# Tempy.net
KiCad netlist of a schematic drawn in EAGLE
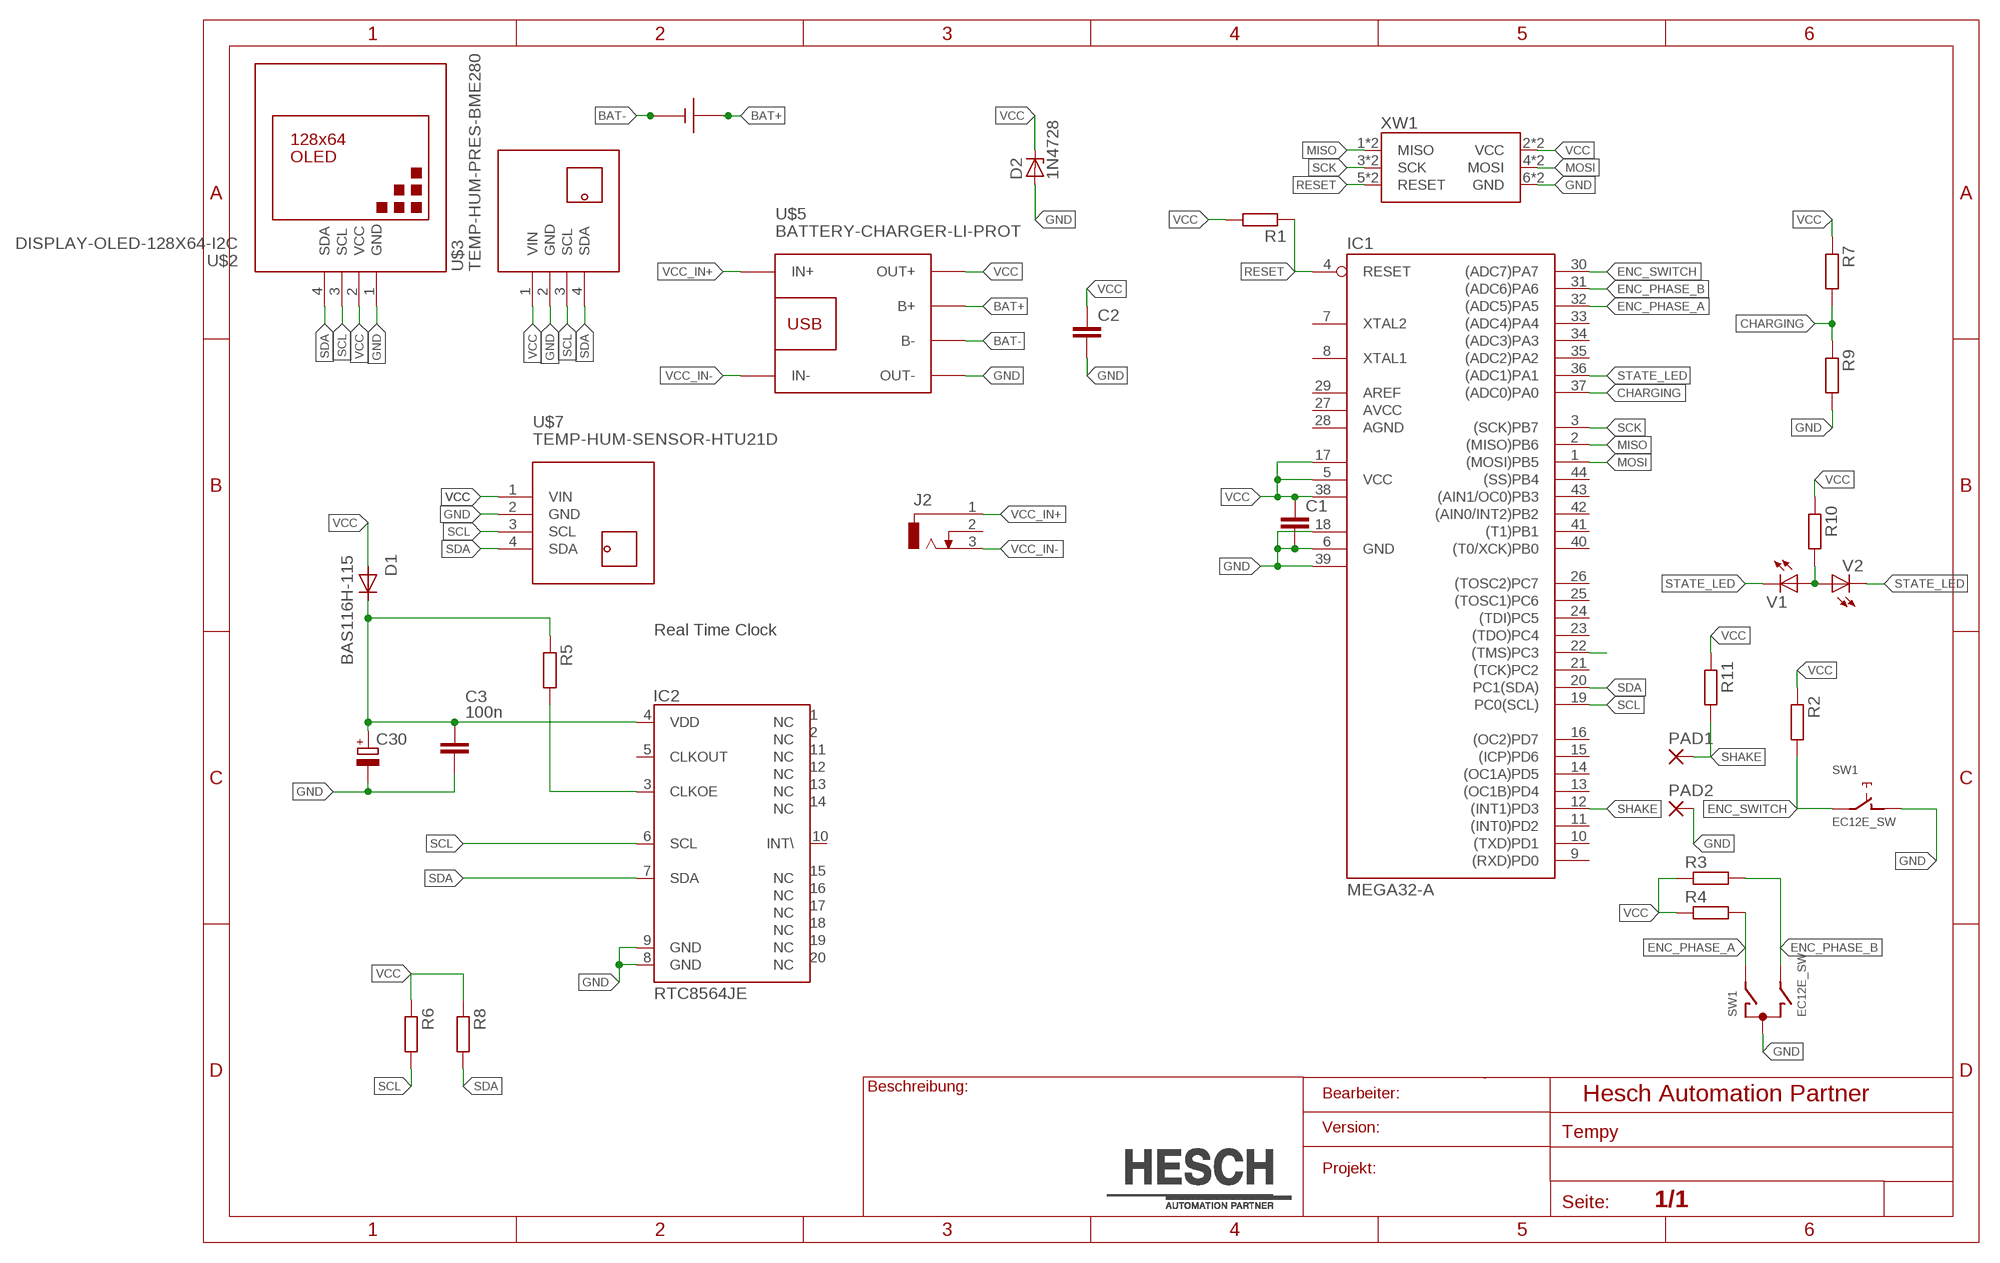
[diagram p0: schematic, sheet 1]

(export (version "E")
  (design (tool "Eeschema 10.0.6"))
  (components
    (comp (ref "C1")
      (value "C-EUC0805K")
      (footprint "eagle-import:C0805K")
      (libsource (lib "eagle-import") (part "C-EUC0805K"))
    )
    (comp (ref "C2")
      (value "C-EUC0805K")
      (footprint "eagle-import:C0805K")
      (libsource (lib "eagle-import") (part "C-EUC0805K"))
    )
    (comp (ref "C3")
      (value "100n")
      (footprint "eagle-import:C0805")
      (libsource (lib "eagle-import") (part "C-EUC0805"))
    )
    (comp (ref "C30")
      (value "PANASONIC-EN&SD-SERIESTHT_1")
      (footprint "eagle-import:PANASONIC_SD_SERIES_STEHEND")
      (libsource (lib "eagle-import") (part "PANASONIC-EN&SD-SERIESTHT_1"))
    )
    (comp (ref "D1")
      (value "BAS116H-115")
      (footprint "eagle-import:SOD123")
      (libsource (lib "eagle-import") (part "BAS116H-115"))
    )
    (comp (ref "D2")
      (value "1N4728")
      (footprint "eagle-import:DO41Z10")
      (libsource (lib "eagle-import") (part "1N4728"))
    )
    (comp (ref "IC1")
      (value "MEGA32-A")
      (footprint "eagle-import:TQFP44")
      (libsource (lib "eagle-import") (part "MEGA32-A"))
    )
    (comp (ref "IC2")
      (value "RTC8564JESMD")
      (footprint "eagle-import:VSOJ20")
      (libsource (lib "eagle-import") (part "RTC8564JESMD"))
    )
    (comp (ref "J2")
      (value "DCJ0303")
      (footprint "eagle-import:DCJ0303")
      (libsource (lib "eagle-import") (part "DCJ0303"))
    )
    (comp (ref "PAD1")
      (value "2,15/1,0")
      (footprint "eagle-import:2,15_1,0")
      (libsource (lib "eagle-import") (part "2,15/1,0"))
    )
    (comp (ref "PAD2")
      (value "2,15/1,0")
      (footprint "eagle-import:2,15_1,0")
      (libsource (lib "eagle-import") (part "2,15/1,0"))
    )
    (comp (ref "R1")
      (value "R-EU_R1206")
      (footprint "eagle-import:R1206")
      (libsource (lib "eagle-import") (part "R-EU_R1206"))
    )
    (comp (ref "R2")
      (value "R-EU_R1206")
      (footprint "eagle-import:R1206")
      (libsource (lib "eagle-import") (part "R-EU_R1206"))
    )
    (comp (ref "R3")
      (value "R-EU_R1206")
      (footprint "eagle-import:R1206")
      (libsource (lib "eagle-import") (part "R-EU_R1206"))
    )
    (comp (ref "R4")
      (value "R-EU_R1206")
      (footprint "eagle-import:R1206")
      (libsource (lib "eagle-import") (part "R-EU_R1206"))
    )
    (comp (ref "R5")
      (value "R-EU_R1206")
      (footprint "eagle-import:R1206")
      (libsource (lib "eagle-import") (part "R-EU_R1206"))
    )
    (comp (ref "R6")
      (value "R-EU_R1206")
      (footprint "eagle-import:R1206")
      (libsource (lib "eagle-import") (part "R-EU_R1206"))
    )
    (comp (ref "R7")
      (value "R-EU_R1206")
      (footprint "eagle-import:R1206")
      (libsource (lib "eagle-import") (part "R-EU_R1206"))
    )
    (comp (ref "R8")
      (value "R-EU_R1206")
      (footprint "eagle-import:R1206")
      (libsource (lib "eagle-import") (part "R-EU_R1206"))
    )
    (comp (ref "R9")
      (value "R-EU_R1206")
      (footprint "eagle-import:R1206")
      (libsource (lib "eagle-import") (part "R-EU_R1206"))
    )
    (comp (ref "R10")
      (value "R-EU_R1206")
      (footprint "eagle-import:R1206")
      (libsource (lib "eagle-import") (part "R-EU_R1206"))
    )
    (comp (ref "R11")
      (value "R-EU_R1206")
      (footprint "eagle-import:R1206")
      (libsource (lib "eagle-import") (part "R-EU_R1206"))
    )
    (comp (ref "SW1")
      (value "EC12E_SW")
      (footprint "eagle-import:ALPS_EC12E_SW")
      (fields (field (name "MPN") "EC12E2424407"))
      (libsource (lib "eagle-import") (part "EC12E_SW"))
    )
    (comp (ref "U$2")
      (value "DISPLAY-OLED-128X64-I2C")
      (footprint "eagle-import:DISPLAY-OLED-128X64-I2C")
      (libsource (lib "eagle-import") (part "DISPLAY-OLED-128X64-I2C"))
    )
    (comp (ref "U$3")
      (value "TEMP-HUM-PRES-BME280")
      (footprint "eagle-import:TEMP-HUM-PRES-BME280")
      (libsource (lib "eagle-import") (part "TEMP-HUM-PRES-BME280"))
    )
    (comp (ref "U$5")
      (value "BATTERY-CHARGER-LI-PROT")
      (footprint "eagle-import:BATTERY-CHARGER-LI-PROT")
      (libsource (lib "eagle-import") (part "BATTERY-CHARGER-LI-PROT"))
    )
    (comp (ref "U$7")
      (value "TEMP-HUM-SENSOR-HTU21D")
      (footprint "eagle-import:TEMP-HUM-SENSOR-HTU21D")
      (libsource (lib "eagle-import") (part "TEMP-HUM-SENSOR-HTU21D"))
    )
    (comp (ref "U$8")
      (value "18650PTH")
      (footprint "eagle-import:18650-CASE-PTH")
      (libsource (lib "eagle-import") (part "18650PTH"))
    )
    (comp (ref "V1")
      (value "0805SMD")
      (footprint "eagle-import:0805")
      (libsource (lib "eagle-import") (part "0805SMD"))
    )
    (comp (ref "V2")
      (value "1206SMD")
      (footprint "eagle-import:1206")
      (libsource (lib "eagle-import") (part "1206SMD"))
    )
    (comp (ref "XW1")
      (value "WSL")
      (footprint "eagle-import:WSL_KOMBI")
      (libsource (lib "eagle-import") (part "WSL"))
    )
  )
  (nets
    (net (code "1") (name "/AGND") (class "Default")
      (node (ref "IC1") (pin "28") (pinfunction "AGND_28") (pintype "power_in"))
    )
    (net (code "2") (name "/AREF") (class "Default")
      (node (ref "IC1") (pin "29") (pinfunction "AREF_29") (pintype "power_in"))
    )
    (net (code "3") (name "/AVCC") (class "Default")
      (node (ref "IC1") (pin "27") (pinfunction "AVCC_27") (pintype "power_in"))
    )
    (net (code "4") (name "BAT+") (class "Default")
      (node (ref "U$5") (pin "B+") (pinfunction "B+_B+") (pintype "bidirectional"))
      (node (ref "U$8") (pin "POS") (pinfunction "POS_POS") (pintype "power_in"))
    )
    (net (code "5") (name "BAT-") (class "Default")
      (node (ref "U$5") (pin "B-") (pinfunction "B-_B-") (pintype "bidirectional"))
      (node (ref "U$8") (pin "NEG") (pinfunction "NEG_NEG") (pintype "power_in"))
    )
    (net (code "6") (name "CHARGING") (class "Default")
      (node (ref "IC1") (pin "37") (pinfunction "(ADC0)PA0_37") (pintype "bidirectional"))
      (node (ref "R7") (pin "2") (pinfunction "2_2") (pintype "passive"))
      (node (ref "R9") (pin "1") (pinfunction "1_1") (pintype "passive"))
    )
    (net (code "7") (name "ENC_PHASE_A") (class "Default")
      (node (ref "IC1") (pin "32") (pinfunction "(ADC5)PA5_32") (pintype "bidirectional"))
      (node (ref "R4") (pin "2") (pinfunction "2_2") (pintype "passive"))
      (node (ref "SW1") (pin "A") (pinfunction "A_A") (pintype "passive"))
    )
    (net (code "8") (name "ENC_PHASE_B") (class "Default")
      (node (ref "IC1") (pin "31") (pinfunction "(ADC6)PA6_31") (pintype "bidirectional"))
      (node (ref "R3") (pin "2") (pinfunction "2_2") (pintype "passive"))
      (node (ref "SW1") (pin "B") (pinfunction "B_B") (pintype "passive"))
    )
    (net (code "9") (name "ENC_SWITCH") (class "Default")
      (node (ref "IC1") (pin "30") (pinfunction "(ADC7)PA7_30") (pintype "bidirectional"))
      (node (ref "R2") (pin "2") (pinfunction "2_2") (pintype "passive"))
      (node (ref "SW1") (pin "E") (pinfunction "2_E") (pintype "passive"))
    )
    (net (code "10") (name "GND") (class "Default")
      (node (ref "C1") (pin "2") (pinfunction "2_2") (pintype "passive"))
      (node (ref "C2") (pin "2") (pinfunction "2_2") (pintype "passive"))
      (node (ref "C3") (pin "2") (pinfunction "2_2") (pintype "passive"))
      (node (ref "C30") (pin "-") (pinfunction "-_-") (pintype "passive"))
      (node (ref "D2") (pin "A") (pinfunction "A_A") (pintype "passive"))
      (node (ref "IC1") (pin "18") (pinfunction "GND1_18") (pintype "power_in"))
      (node (ref "IC1") (pin "39") (pinfunction "GND2_39") (pintype "power_in"))
      (node (ref "IC1") (pin "6") (pinfunction "GND_6") (pintype "power_in"))
      (node (ref "IC2") (pin "8") (pinfunction "GND_8") (pintype "power_in"))
      (node (ref "IC2") (pin "9") (pinfunction "GND_9") (pintype "power_in"))
      (node (ref "PAD2") (pin "1") (pinfunction "P_1") (pintype "passive"))
      (node (ref "R9") (pin "2") (pinfunction "2_2") (pintype "passive"))
      (node (ref "SW1") (pin "C") (pinfunction "C_C") (pintype "passive"))
      (node (ref "SW1") (pin "D") (pinfunction "1_D") (pintype "passive"))
      (node (ref "U$2") (pin "1") (pinfunction "GND_1") (pintype "power_in"))
      (node (ref "U$3") (pin "2") (pinfunction "GND_2") (pintype "power_in"))
      (node (ref "U$5") (pin "OUT-") (pinfunction "OUT-_OUT-") (pintype "bidirectional"))
      (node (ref "U$7") (pin "2") (pinfunction "GND_2") (pintype "power_in"))
      (node (ref "XW1") (pin "6") (pinfunction "GND_6") (pintype "power_in"))
      (node (ref "XW1") (pin "6.1") (pinfunction "GND_6.1") (pintype "power_in"))
    )
    (net (code "11") (name "MISO") (class "Default")
      (node (ref "IC1") (pin "2") (pinfunction "(MISO)PB6_2") (pintype "bidirectional"))
      (node (ref "XW1") (pin "1") (pinfunction "MISO_1") (pintype "bidirectional"))
      (node (ref "XW1") (pin "1.1") (pinfunction "MISO_1.1") (pintype "bidirectional"))
    )
    (net (code "12") (name "MOSI") (class "Default")
      (node (ref "IC1") (pin "1") (pinfunction "(MOSI)PB5_1") (pintype "bidirectional"))
      (node (ref "XW1") (pin "4") (pinfunction "MOSI_4") (pintype "bidirectional"))
      (node (ref "XW1") (pin "4.1") (pinfunction "MOSI_4.1") (pintype "bidirectional"))
    )
    (net (code "13") (name "Net-(IC2-CLKOE)") (class "Default")
      (node (ref "IC2") (pin "3") (pinfunction "CLKOE_3") (pintype "input"))
      (node (ref "R5") (pin "2") (pinfunction "2_2") (pintype "passive"))
    )
    (net (code "14") (name "Net-(IC2-VDD)") (class "Default")
      (node (ref "C3") (pin "1") (pinfunction "1_1") (pintype "passive"))
      (node (ref "C30") (pin "+") (pinfunction "+_+") (pintype "passive"))
      (node (ref "D1") (pin "C") (pinfunction "C_C") (pintype "passive"))
      (node (ref "IC2") (pin "4") (pinfunction "VDD_4") (pintype "power_in"))
      (node (ref "R5") (pin "1") (pinfunction "1_1") (pintype "passive"))
    )
    (net (code "15") (name "Net-(R10-Pad2)") (class "Default")
      (node (ref "R10") (pin "2") (pinfunction "2_2") (pintype "passive"))
      (node (ref "V1") (pin "A") (pinfunction "A_A") (pintype "passive"))
      (node (ref "V2") (pin "A") (pinfunction "A_A") (pintype "passive"))
    )
    (net (code "16") (name "RESET") (class "Default")
      (node (ref "IC1") (pin "4") (pinfunction "RESET_4") (pintype "input"))
      (node (ref "R1") (pin "1") (pinfunction "1_1") (pintype "passive"))
      (node (ref "XW1") (pin "5") (pinfunction "RESET_5") (pintype "bidirectional"))
      (node (ref "XW1") (pin "5.1") (pinfunction "RESET_5.1") (pintype "bidirectional"))
    )
    (net (code "17") (name "SCK") (class "Default")
      (node (ref "IC1") (pin "3") (pinfunction "(SCK)PB7_3") (pintype "bidirectional"))
      (node (ref "XW1") (pin "3") (pinfunction "SCK_3") (pintype "bidirectional"))
      (node (ref "XW1") (pin "3.1") (pinfunction "SCK_3.1") (pintype "bidirectional"))
    )
    (net (code "18") (name "SCL") (class "Default")
      (node (ref "IC1") (pin "19") (pinfunction "PC0(SCL)_19") (pintype "bidirectional"))
      (node (ref "IC2") (pin "6") (pinfunction "SCL_6") (pintype "input"))
      (node (ref "R6") (pin "2") (pinfunction "2_2") (pintype "passive"))
      (node (ref "U$2") (pin "3") (pinfunction "SCL_3") (pintype "bidirectional"))
      (node (ref "U$3") (pin "3") (pinfunction "SCL_3") (pintype "bidirectional"))
      (node (ref "U$7") (pin "3") (pinfunction "SCL_3") (pintype "bidirectional"))
    )
    (net (code "19") (name "SDA") (class "Default")
      (node (ref "IC1") (pin "20") (pinfunction "PC1(SDA)_20") (pintype "bidirectional"))
      (node (ref "IC2") (pin "7") (pinfunction "SDA_7") (pintype "bidirectional"))
      (node (ref "R8") (pin "2") (pinfunction "2_2") (pintype "passive"))
      (node (ref "U$2") (pin "4") (pinfunction "SDA_4") (pintype "bidirectional"))
      (node (ref "U$3") (pin "4") (pinfunction "SDA_4") (pintype "bidirectional"))
      (node (ref "U$7") (pin "4") (pinfunction "SDA_4") (pintype "bidirectional"))
    )
    (net (code "20") (name "SHAKE") (class "Default")
      (node (ref "IC1") (pin "12") (pinfunction "(INT1)PD3_12") (pintype "bidirectional"))
      (node (ref "PAD1") (pin "1") (pinfunction "P_1") (pintype "passive"))
      (node (ref "R11") (pin "2") (pinfunction "2_2") (pintype "passive"))
    )
    (net (code "21") (name "STATE_LED") (class "Default")
      (node (ref "IC1") (pin "36") (pinfunction "(ADC1)PA1_36") (pintype "bidirectional"))
      (node (ref "V1") (pin "K") (pinfunction "K_K") (pintype "passive"))
      (node (ref "V2") (pin "K") (pinfunction "K_K") (pintype "passive"))
    )
    (net (code "22") (name "VCC") (class "Default")
      (node (ref "C1") (pin "1") (pinfunction "1_1") (pintype "passive"))
      (node (ref "C2") (pin "1") (pinfunction "1_1") (pintype "passive"))
      (node (ref "D1") (pin "A") (pinfunction "A_A") (pintype "passive"))
      (node (ref "D2") (pin "C") (pinfunction "C_C") (pintype "passive"))
      (node (ref "IC1") (pin "17") (pinfunction "VCC1_17") (pintype "power_in"))
      (node (ref "IC1") (pin "38") (pinfunction "VCC2_38") (pintype "power_in"))
      (node (ref "IC1") (pin "5") (pinfunction "VCC_5") (pintype "power_in"))
      (node (ref "R1") (pin "2") (pinfunction "2_2") (pintype "passive"))
      (node (ref "R10") (pin "1") (pinfunction "1_1") (pintype "passive"))
      (node (ref "R11") (pin "1") (pinfunction "1_1") (pintype "passive"))
      (node (ref "R2") (pin "1") (pinfunction "1_1") (pintype "passive"))
      (node (ref "R3") (pin "1") (pinfunction "1_1") (pintype "passive"))
      (node (ref "R4") (pin "1") (pinfunction "1_1") (pintype "passive"))
      (node (ref "R6") (pin "1") (pinfunction "1_1") (pintype "passive"))
      (node (ref "R7") (pin "1") (pinfunction "1_1") (pintype "passive"))
      (node (ref "R8") (pin "1") (pinfunction "1_1") (pintype "passive"))
      (node (ref "U$2") (pin "2") (pinfunction "VCC_2") (pintype "power_in"))
      (node (ref "U$3") (pin "1") (pinfunction "VIN_1") (pintype "power_in"))
      (node (ref "U$5") (pin "OUT+") (pinfunction "OUT+_OUT+") (pintype "bidirectional"))
      (node (ref "U$7") (pin "1") (pinfunction "VIN_1") (pintype "power_in"))
      (node (ref "XW1") (pin "2") (pinfunction "VCC_2") (pintype "power_in"))
      (node (ref "XW1") (pin "2.1") (pinfunction "VCC_2.1") (pintype "power_in"))
    )
    (net (code "23") (name "VCC_IN+") (class "Default")
      (node (ref "J2") (pin "1") (pinfunction "1_1") (pintype "passive"))
      (node (ref "U$5") (pin "IN+") (pinfunction "IN+_IN+") (pintype "bidirectional"))
    )
    (net (code "24") (name "VCC_IN-") (class "Default")
      (node (ref "J2") (pin "3") (pinfunction "3_3") (pintype "passive"))
      (node (ref "U$5") (pin "IN-") (pinfunction "IN-_IN-") (pintype "bidirectional"))
    )
    (net (code "25") (name "unconnected-(IC1-(ADC2)PA2-Pad35)") (class "Default")
      (node (ref "IC1") (pin "35") (pinfunction "(ADC2)PA2_35") (pintype "bidirectional"))
    )
    (net (code "26") (name "unconnected-(IC1-(ADC3)PA3-Pad34)") (class "Default")
      (node (ref "IC1") (pin "34") (pinfunction "(ADC3)PA3_34") (pintype "bidirectional"))
    )
    (net (code "27") (name "unconnected-(IC1-(ADC4)PA4-Pad33)") (class "Default")
      (node (ref "IC1") (pin "33") (pinfunction "(ADC4)PA4_33") (pintype "bidirectional"))
    )
    (net (code "28") (name "unconnected-(IC1-(AIN0{slash}INT2)PB2-Pad42)") (class "Default")
      (node (ref "IC1") (pin "42") (pinfunction "(AIN0/INT2)PB2_42") (pintype "bidirectional"))
    )
    (net (code "29") (name "unconnected-(IC1-(AIN1{slash}OC0)PB3-Pad43)") (class "Default")
      (node (ref "IC1") (pin "43") (pinfunction "(AIN1/OC0)PB3_43") (pintype "bidirectional"))
    )
    (net (code "30") (name "unconnected-(IC1-(ICP)PD6-Pad15)") (class "Default")
      (node (ref "IC1") (pin "15") (pinfunction "(ICP)PD6_15") (pintype "bidirectional"))
    )
    (net (code "31") (name "unconnected-(IC1-(INT0)PD2-Pad11)") (class "Default")
      (node (ref "IC1") (pin "11") (pinfunction "(INT0)PD2_11") (pintype "bidirectional"))
    )
    (net (code "32") (name "unconnected-(IC1-(OC1A)PD5-Pad14)") (class "Default")
      (node (ref "IC1") (pin "14") (pinfunction "(OC1A)PD5_14") (pintype "bidirectional"))
    )
    (net (code "33") (name "unconnected-(IC1-(OC1B)PD4-Pad13)") (class "Default")
      (node (ref "IC1") (pin "13") (pinfunction "(OC1B)PD4_13") (pintype "bidirectional"))
    )
    (net (code "34") (name "unconnected-(IC1-(OC2)PD7-Pad16)") (class "Default")
      (node (ref "IC1") (pin "16") (pinfunction "(OC2)PD7_16") (pintype "bidirectional"))
    )
    (net (code "35") (name "unconnected-(IC1-(RXD)PD0-Pad9)") (class "Default")
      (node (ref "IC1") (pin "9") (pinfunction "(RXD)PD0_9") (pintype "bidirectional"))
    )
    (net (code "36") (name "unconnected-(IC1-(SS)PB4-Pad44)") (class "Default")
      (node (ref "IC1") (pin "44") (pinfunction "(SS)PB4_44") (pintype "bidirectional"))
    )
    (net (code "37") (name "unconnected-(IC1-(T0{slash}XCK)PB0-Pad40)") (class "Default")
      (node (ref "IC1") (pin "40") (pinfunction "(T0/XCK)PB0_40") (pintype "bidirectional"))
    )
    (net (code "38") (name "unconnected-(IC1-(T1)PB1-Pad41)") (class "Default")
      (node (ref "IC1") (pin "41") (pinfunction "(T1)PB1_41") (pintype "bidirectional"))
    )
    (net (code "39") (name "unconnected-(IC1-(TCK)PC2-Pad21)") (class "Default")
      (node (ref "IC1") (pin "21") (pinfunction "(TCK)PC2_21") (pintype "bidirectional"))
    )
    (net (code "40") (name "unconnected-(IC1-(TDI)PC5-Pad24)") (class "Default")
      (node (ref "IC1") (pin "24") (pinfunction "(TDI)PC5_24") (pintype "bidirectional"))
    )
    (net (code "41") (name "unconnected-(IC1-(TDO)PC4-Pad23)") (class "Default")
      (node (ref "IC1") (pin "23") (pinfunction "(TDO)PC4_23") (pintype "bidirectional"))
    )
    (net (code "42") (name "unconnected-(IC1-(TMS)PC3-Pad22)") (class "Default")
      (node (ref "IC1") (pin "22") (pinfunction "(TMS)PC3_22") (pintype "bidirectional"))
    )
    (net (code "43") (name "unconnected-(IC1-(TOSC1)PC6-Pad25)") (class "Default")
      (node (ref "IC1") (pin "25") (pinfunction "(TOSC1)PC6_25") (pintype "bidirectional"))
    )
    (net (code "44") (name "unconnected-(IC1-(TOSC2)PC7-Pad26)") (class "Default")
      (node (ref "IC1") (pin "26") (pinfunction "(TOSC2)PC7_26") (pintype "bidirectional"))
    )
    (net (code "45") (name "unconnected-(IC1-(TXD)PD1-Pad10)") (class "Default")
      (node (ref "IC1") (pin "10") (pinfunction "(TXD)PD1_10") (pintype "bidirectional"))
    )
    (net (code "46") (name "unconnected-(IC1-XTAL1-Pad8)") (class "Default")
      (node (ref "IC1") (pin "8") (pinfunction "XTAL1_8") (pintype "bidirectional"))
    )
    (net (code "47") (name "unconnected-(IC1-XTAL2-Pad7)") (class "Default")
      (node (ref "IC1") (pin "7") (pinfunction "XTAL2_7") (pintype "bidirectional"))
    )
    (net (code "48") (name "unconnected-(IC2-CLKOUT-Pad5)") (class "Default")
      (node (ref "IC2") (pin "5") (pinfunction "CLKOUT_5") (pintype "output"))
    )
    (net (code "49") (name "unconnected-(IC2-INT\\-Pad10)") (class "Default")
      (node (ref "IC2") (pin "10") (pinfunction "INT\\_10") (pintype "output"))
    )
    (net (code "50") (name "unconnected-(IC2-NC-Pad1)") (class "Default")
      (node (ref "IC2") (pin "1") (pinfunction "NC_1") (pintype "no_connect"))
    )
    (net (code "51") (name "unconnected-(IC2-NC-Pad2)") (class "Default")
      (node (ref "IC2") (pin "2") (pinfunction "NC_2") (pintype "no_connect"))
    )
    (net (code "52") (name "unconnected-(IC2-NC-Pad11)") (class "Default")
      (node (ref "IC2") (pin "11") (pinfunction "NC_11") (pintype "no_connect"))
    )
    (net (code "53") (name "unconnected-(IC2-NC-Pad12)") (class "Default")
      (node (ref "IC2") (pin "12") (pinfunction "NC_12") (pintype "no_connect"))
    )
    (net (code "54") (name "unconnected-(IC2-NC-Pad13)") (class "Default")
      (node (ref "IC2") (pin "13") (pinfunction "NC_13") (pintype "no_connect"))
    )
    (net (code "55") (name "unconnected-(IC2-NC-Pad14)") (class "Default")
      (node (ref "IC2") (pin "14") (pinfunction "NC_14") (pintype "no_connect"))
    )
    (net (code "56") (name "unconnected-(IC2-NC-Pad15)") (class "Default")
      (node (ref "IC2") (pin "15") (pinfunction "NC_15") (pintype "no_connect"))
    )
    (net (code "57") (name "unconnected-(IC2-NC-Pad16)") (class "Default")
      (node (ref "IC2") (pin "16") (pinfunction "NC_16") (pintype "no_connect"))
    )
    (net (code "58") (name "unconnected-(IC2-NC-Pad17)") (class "Default")
      (node (ref "IC2") (pin "17") (pinfunction "NC_17") (pintype "no_connect"))
    )
    (net (code "59") (name "unconnected-(IC2-NC-Pad18)") (class "Default")
      (node (ref "IC2") (pin "18") (pinfunction "NC_18") (pintype "no_connect"))
    )
    (net (code "60") (name "unconnected-(IC2-NC-Pad19)") (class "Default")
      (node (ref "IC2") (pin "19") (pinfunction "NC_19") (pintype "no_connect"))
    )
    (net (code "61") (name "unconnected-(IC2-NC-Pad20)") (class "Default")
      (node (ref "IC2") (pin "20") (pinfunction "NC_20") (pintype "no_connect"))
    )
    (net (code "62") (name "unconnected-(J2-Pad2)") (class "Default")
      (node (ref "J2") (pin "2") (pinfunction "2_2") (pintype "passive"))
    )
  )
)
